# main-unit-psu.net
KiCad netlist of a schematic drawn in EAGLE
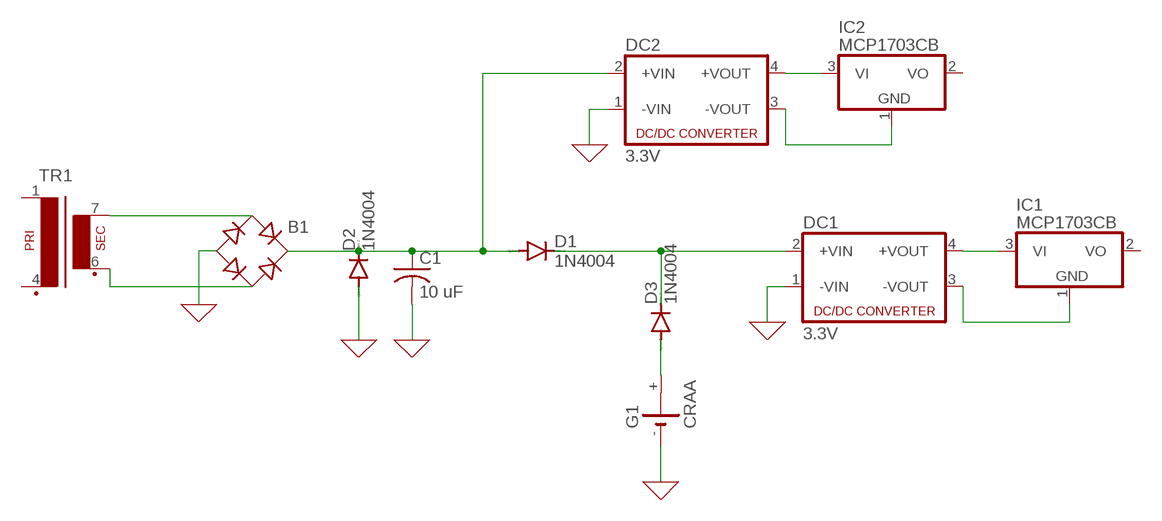
[diagram p0: schematic, sheet 1]

(export (version "E")
  (design (tool "Eeschema 10.0.6"))
  (components
    (comp (ref "B1")
      (value "B-DIL")
      (footprint "eagle-import:B-DIL")
      (libsource (lib "eagle-import") (part "B-DIL"))
    )
    (comp (ref "C1")
      (value "10 uF")
      (footprint "eagle-import:C050-024X044")
      (fields (field (name "MF") "KEMET") (field (name "MPN") "ESW106M025AC3AA"))
      (libsource (lib "eagle-import") (part "C-US050-024X044"))
    )
    (comp (ref "D1")
      (value "1N4004")
      (footprint "eagle-import:DO41-10")
      (fields (field (name "MF") "ONSEMI") (field (name "MPN") "1N4004RLG"))
      (libsource (lib "eagle-import") (part "1N4004"))
    )
    (comp (ref "D2")
      (value "1N4004")
      (footprint "eagle-import:DO41-10")
      (fields (field (name "MF") "ONSEMI") (field (name "MPN") "1N4004RLG"))
      (libsource (lib "eagle-import") (part "1N4004"))
    )
    (comp (ref "D3")
      (value "1N4004")
      (footprint "eagle-import:DO41-10")
      (fields (field (name "MF") "ONSEMI") (field (name "MPN") "1N4004RLG"))
      (libsource (lib "eagle-import") (part "1N4004"))
    )
    (comp (ref "DC1")
      (value "3.3V")
      (footprint "eagle-import:NME")
      (fields
        (field (name "MF") "C & D TECHNOLOGIES, INC")
        (field (name "MPN") "NME1205D")
        (field (name "MF_1") "MURATA POWER SOLUTIONS")
        (field (name "MPN_1") "CME0303S3C")
        (field (name "OC_NEWARK") "29X1501")
      )
      (libsource (lib "eagle-import") (part "NME"))
    )
    (comp (ref "DC2")
      (value "3.3V")
      (footprint "eagle-import:NME")
      (fields
        (field (name "MF") "C & D TECHNOLOGIES, INC")
        (field (name "MPN") "NME1205D")
        (field (name "MF_1") "MURATA POWER SOLUTIONS")
        (field (name "MPN_1") "CME0303S3C")
        (field (name "OC_NEWARK") "29X1501")
      )
      (libsource (lib "eagle-import") (part "NME"))
    )
    (comp (ref "G1")
      (value "CRAA")
      (footprint "eagle-import:CRAA")
      (libsource (lib "eagle-import") (part "CRAA"))
    )
    (comp (ref "IC1")
      (value "MCP1703CB")
      (footprint "eagle-import:SOT23")
      (libsource (lib "eagle-import") (part "MCP1703CB"))
    )
    (comp (ref "IC2")
      (value "MCP1703CB")
      (footprint "eagle-import:SOT23")
      (libsource (lib "eagle-import") (part "MCP1703CB"))
    )
    (comp (ref "TR1")
      (value "EE20-1")
      (footprint "eagle-import:EE20-1")
      (fields (field (name "MF") "TRIAD MAGNETICS") (field (name "MPN") "TCT3-11E07AE"))
      (libsource (lib "eagle-import") (part "EE20-1"))
    )
  )
  (nets
    (net (code "1") (name "GND") (class "Default")
      (node (ref "B1") (pin "-") (pinfunction "-_-") (pintype "passive"))
      (node (ref "C1") (pin "2") (pinfunction "2_2") (pintype "passive"))
      (node (ref "D2") (pin "A") (pinfunction "A_A") (pintype "passive"))
      (node (ref "DC1") (pin "1") (pinfunction "-VIN_1") (pintype "passive"))
      (node (ref "DC2") (pin "1") (pinfunction "-VIN_1") (pintype "passive"))
      (node (ref "G1") (pin "-") (pinfunction "-_-") (pintype "passive"))
    )
    (net (code "2") (name "Net-(D3-PadA)") (class "Default")
      (node (ref "D3") (pin "A") (pinfunction "A_A") (pintype "passive"))
      (node (ref "G1") (pin "+") (pinfunction "+_+") (pintype "passive"))
    )
    (net (code "3") (name "Net-(DC1-+VIN)") (class "Default")
      (node (ref "D1") (pin "C") (pinfunction "C_C") (pintype "passive"))
      (node (ref "D3") (pin "C") (pinfunction "C_C") (pintype "passive"))
      (node (ref "DC1") (pin "2") (pinfunction "+VIN_2") (pintype "passive"))
    )
    (net (code "4") (name "Net-(DC1-+VOUT)") (class "Default")
      (node (ref "DC1") (pin "4") (pinfunction "+VOUT_4") (pintype "passive"))
      (node (ref "IC1") (pin "3") (pinfunction "VI_3") (pintype "input"))
    )
    (net (code "5") (name "Net-(DC1--VOUT)") (class "Default")
      (node (ref "DC1") (pin "3") (pinfunction "-VOUT_3") (pintype "passive"))
      (node (ref "IC1") (pin "1") (pinfunction "GND_1") (pintype "passive"))
    )
    (net (code "6") (name "Net-(DC2-+VIN)") (class "Default")
      (node (ref "B1") (pin "+") (pinfunction "+_+") (pintype "passive"))
      (node (ref "C1") (pin "1") (pinfunction "1_1") (pintype "passive"))
      (node (ref "D1") (pin "A") (pinfunction "A_A") (pintype "passive"))
      (node (ref "D2") (pin "C") (pinfunction "C_C") (pintype "passive"))
      (node (ref "DC2") (pin "2") (pinfunction "+VIN_2") (pintype "passive"))
    )
    (net (code "7") (name "Net-(DC2-+VOUT)") (class "Default")
      (node (ref "DC2") (pin "4") (pinfunction "+VOUT_4") (pintype "passive"))
      (node (ref "IC2") (pin "3") (pinfunction "VI_3") (pintype "input"))
    )
    (net (code "8") (name "Net-(DC2--VOUT)") (class "Default")
      (node (ref "DC2") (pin "3") (pinfunction "-VOUT_3") (pintype "passive"))
      (node (ref "IC2") (pin "1") (pinfunction "GND_1") (pintype "passive"))
    )
    (net (code "9") (name "Net-(TR1-S3)") (class "Default")
      (node (ref "B1") (pin "AC2") (pinfunction "AC2_AC2") (pintype "passive"))
      (node (ref "TR1") (pin "6") (pinfunction "S3_6") (pintype "passive"))
    )
    (net (code "10") (name "Net-(TR1-S4)") (class "Default")
      (node (ref "B1") (pin "AC1") (pinfunction "AC1_AC1") (pintype "passive"))
      (node (ref "TR1") (pin "7") (pinfunction "S4_7") (pintype "passive"))
    )
    (net (code "11") (name "unconnected-(G1-+-Pad+@1)") (class "Default")
      (node (ref "G1") (pin "+@1") (pinfunction "+_+@1") (pintype "passive"))
    )
    (net (code "12") (name "unconnected-(IC1-VO-Pad2)") (class "Default")
      (node (ref "IC1") (pin "2") (pinfunction "VO_2") (pintype "passive"))
    )
    (net (code "13") (name "unconnected-(IC2-VO-Pad2)") (class "Default")
      (node (ref "IC2") (pin "2") (pinfunction "VO_2") (pintype "passive"))
    )
    (net (code "14") (name "unconnected-(TR1-P1-Pad1)") (class "Default")
      (node (ref "TR1") (pin "1") (pinfunction "P1_1") (pintype "passive"))
    )
    (net (code "15") (name "unconnected-(TR1-P2-Pad4)") (class "Default")
      (node (ref "TR1") (pin "4") (pinfunction "P2_4") (pintype "passive"))
    )
  )
)
